# Constant_Current.net
KiCad netlist of a schematic drawn in Altium Designer
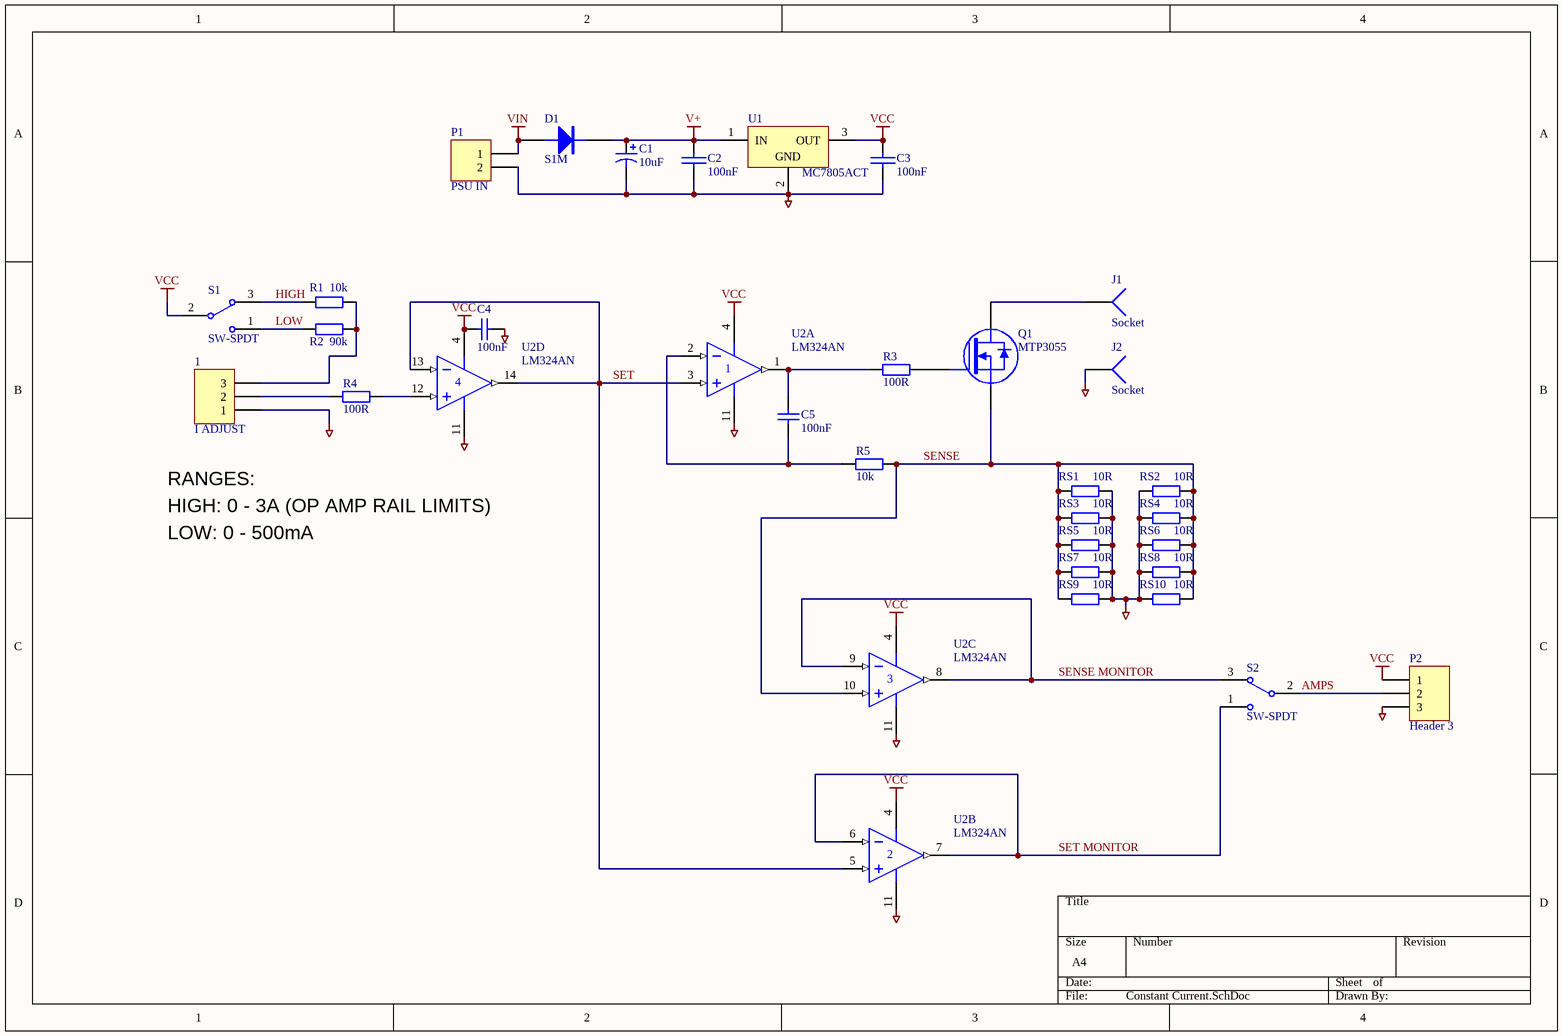
[diagram p0: Constant Current.SchDoc]

(export (version "E")
  (design (tool "Eeschema 10.0.6"))
  (components
    (comp (ref "1")
      (value "I ADJUST")
      (footprint "PCB POT 17MM")
      (description "Header, 3-Pin")
      (fields (field (name "PUBLISHER") "Altium Limited"))
      (libsource (lib "Miscellaneous Connectors") (part "Header 3"))
    )
    (comp (ref "C1")
      (value "10uF")
      (footprint "CAP E CASE")
      (description "Polarized Capacitor (Radial)")
      (libsource (lib "Miscellaneous Devices") (part "Cap Pol1"))
    )
    (comp (ref "C2")
      (value "100nF")
      (footprint "LowCostLabs:CAP 0805")
      (description "CAPACITOR SMD 0603")
      (fields (field (name "MOUSER PART NO.") "81-GCM188R71C104KA7D") (field (name "MANUFACTURER") "Murata"))
      (libsource (lib "Mi-Call Schematic") (part "CAP"))
    )
    (comp (ref "C3")
      (value "100nF")
      (footprint "LowCostLabs:CAP 0805")
      (description "CAPACITOR SMD 0603")
      (fields (field (name "MOUSER PART NO.") "81-GCM188R71C104KA7D") (field (name "MANUFACTURER") "Murata"))
      (libsource (lib "Mi-Call Schematic") (part "CAP"))
    )
    (comp (ref "C4")
      (value "100nF")
      (footprint "LowCostLabs:CAP 0805")
      (description "Capacitor")
      (fields
        (field (name "MANUFACTURER") "YAEGO")
        (field (name "MANUFACTURER PART NO.") "CC0603ZRY5V9BB104")
      )
      (libsource (lib "Miscellaneous Devices") (part "Cap"))
    )
    (comp (ref "C5")
      (value "100nF")
      (footprint "LowCostLabs:CAP 0805")
      (description "Capacitor")
      (fields
        (field (name "MANUFACTURER") "YAEGO")
        (field (name "MANUFACTURER PART NO.") "CC0603ZRY5V9BB104")
      )
      (libsource (lib "Miscellaneous Devices") (part "Cap"))
    )
    (comp (ref "D1")
      (value "S1M")
      (footprint "DO-214AC")
      (description "DIODE, POWER")
      (fields (field (name "MOUSER PART NO.") "821-S1M") (field (name "MANUFACTURER") "Taiwan Semiconductor"))
      (libsource (lib "*") (part "DIODE"))
    )
    (comp (ref "J1")
      (value "Socket")
      (footprint "TP")
      (fields (field (name "PUBLISHER") "Altium Limited"))
      (libsource (lib "Miscellaneous Connectors") (part "Socket"))
    )
    (comp (ref "J2")
      (value "Socket")
      (footprint "TP")
      (fields (field (name "PUBLISHER") "Altium Limited"))
      (libsource (lib "Miscellaneous Connectors") (part "Socket"))
    )
    (comp (ref "P1")
      (value "PSU IN")
      (footprint "5.08mm HEADER 2 Way RA- With Socket")
      (description "Header, 2-Pin")
      (fields (field (name "PUBLISHER") "Altium Limited"))
      (libsource (lib "Miscellaneous Connectors") (part "Header 2"))
    )
    (comp (ref "P2")
      (value "Header 3")
      (footprint "HDR1X3")
      (description "Header, 3-Pin")
      (fields (field (name "PUBLISHER") "Altium Limited"))
      (libsource (lib "") (part "Header 3_1"))
    )
    (comp (ref "Q1")
      (value "MTP3055")
      (footprint "TO-220AB")
      (description "N-Channel MOSFET")
      (libsource (lib "Schlib1") (part "MOSFET-N4"))
    )
    (comp (ref "R1")
      (value "10k")
      (footprint "LowCostLabs:RES 0805")
      (description "Resistor")
      (fields (field (name "Comment") "0805"))
      (libsource (lib "") (part "Res2_1"))
    )
    (comp (ref "R2")
      (value "90k")
      (footprint "LowCostLabs:RES 0805")
      (description "Resistor")
      (fields (field (name "Comment") "0805"))
      (libsource (lib "") (part "Res2_1"))
    )
    (comp (ref "R3")
      (value "100R")
      (footprint "LowCostLabs:RES 0805")
      (description "Resistor")
      (fields (field (name "Comment") "0805"))
      (libsource (lib "") (part "Res2_1"))
    )
    (comp (ref "R4")
      (value "100R")
      (footprint "LowCostLabs:RES 0805")
      (description "Resistor")
      (fields (field (name "Comment") "0805"))
      (libsource (lib "") (part "Res2_1"))
    )
    (comp (ref "R5")
      (value "10k")
      (footprint "LowCostLabs:RES 0805")
      (description "Resistor")
      (fields (field (name "Comment") "0805"))
      (libsource (lib "") (part "Res2_1"))
    )
    (comp (ref "RS1")
      (value "10R")
      (footprint "LowCostLabs:RES 1210")
      (description "Resistor")
      (fields (field (name "Comment") "0805"))
      (libsource (lib "Miscellaneous Devices") (part "Res2"))
    )
    (comp (ref "RS2")
      (value "10R")
      (footprint "LowCostLabs:RES 1210")
      (description "Resistor")
      (fields (field (name "Comment") "0805"))
      (libsource (lib "Miscellaneous Devices") (part "Res2"))
    )
    (comp (ref "RS3")
      (value "10R")
      (footprint "LowCostLabs:RES 1210")
      (description "Resistor")
      (fields (field (name "Comment") "0805"))
      (libsource (lib "Miscellaneous Devices") (part "Res2"))
    )
    (comp (ref "RS4")
      (value "10R")
      (footprint "LowCostLabs:RES 1210")
      (description "Resistor")
      (fields (field (name "Comment") "0805"))
      (libsource (lib "Miscellaneous Devices") (part "Res2"))
    )
    (comp (ref "RS5")
      (value "10R")
      (footprint "LowCostLabs:RES 1210")
      (description "Resistor")
      (fields (field (name "Comment") "0805"))
      (libsource (lib "Miscellaneous Devices") (part "Res2"))
    )
    (comp (ref "RS6")
      (value "10R")
      (footprint "LowCostLabs:RES 1210")
      (description "Resistor")
      (fields (field (name "Comment") "0805"))
      (libsource (lib "Miscellaneous Devices") (part "Res2"))
    )
    (comp (ref "RS7")
      (value "10R")
      (footprint "LowCostLabs:RES 1210")
      (description "Resistor")
      (fields (field (name "Comment") "0805"))
      (libsource (lib "Miscellaneous Devices") (part "Res2"))
    )
    (comp (ref "RS8")
      (value "10R")
      (footprint "LowCostLabs:RES 1210")
      (description "Resistor")
      (fields (field (name "Comment") "0805"))
      (libsource (lib "Miscellaneous Devices") (part "Res2"))
    )
    (comp (ref "RS9")
      (value "10R")
      (footprint "LowCostLabs:RES 1210")
      (description "Resistor")
      (fields (field (name "Comment") "0805"))
      (libsource (lib "Miscellaneous Devices") (part "Res2"))
    )
    (comp (ref "RS10")
      (value "10R")
      (footprint "LowCostLabs:RES 1210")
      (description "Resistor")
      (fields (field (name "Comment") "0805"))
      (libsource (lib "Miscellaneous Devices") (part "Res2"))
    )
    (comp (ref "S1")
      (value "SW-SPDT")
      (footprint "SPDT MINI TOGGLE (BOARD MOUNT)")
      (description "SPDT Subminiature Toggle Switch, Right Angle Mounting, Vertical Actuation")
      (fields (field (name "PUBLISHER") "Altium Limited"))
      (libsource (lib "Miscellaneous Devices") (part "SW-SPDT"))
    )
    (comp (ref "S2")
      (value "SW-SPDT")
      (footprint "SPDT MINI TOGGLE (BOARD MOUNT)")
      (description "SPDT Subminiature Toggle Switch, Right Angle Mounting, Vertical Actuation")
      (fields (field (name "PUBLISHER") "Altium Limited"))
      (libsource (lib "Miscellaneous Devices") (part "SW-SPDT"))
    )
    (comp (ref "U1")
      (value "MC7805ACT")
      (footprint "SOT89")
      (description "3-Terminal Positive Fixed Voltage Regulator")
      (fields
        (field (name "MOUSER PART NO.") "512-LM7805ACT")
        (field (name "MANUFACTURER") "Fairchild Semiconductor")
      )
      (libsource (lib "Motorola Power Mgt Voltage Regulator") (part "MC7805ACT"))
    )
    (comp (ref "U2")
      (value "LM324AN")
      (footprint "LowCostLabs:SOIC-14")
      (description "Quadruple Operational Amplifier")
      (fields (field (name "MANUFACTURER") "ST MICRO") (field (name "MOUSER PART NO.") "511-LM324AN"))
      (libsource (lib "TI Operational Amplifier") (part "LM324AN"))
    )
  )
  (nets
    (net (code "1") (name "/AMPS") (class "Default")
      (node (ref "P2") (pin "2") (pinfunction "2_2") (pintype "passive"))
      (node (ref "S2") (pin "2") (pinfunction "2_2") (pintype "passive"))
    )
    (net (code "2") (name "/HIGH") (class "Default")
      (node (ref "R1") (pin "1") (pinfunction "1_1") (pintype "passive"))
      (node (ref "S1") (pin "3") (pinfunction "3_3") (pintype "passive"))
    )
    (net (code "3") (name "/LOW") (class "Default")
      (node (ref "R2") (pin "1") (pinfunction "1_1") (pintype "passive"))
      (node (ref "S1") (pin "1") (pinfunction "1_1") (pintype "passive"))
    )
    (net (code "4") (name "/SENSE") (class "Default")
      (node (ref "Q1") (pin "3") (pinfunction "S_3") (pintype "passive"))
      (node (ref "R5") (pin "2") (pinfunction "2_2") (pintype "passive"))
      (node (ref "RS1") (pin "2") (pinfunction "2_2") (pintype "passive"))
      (node (ref "RS10") (pin "1") (pinfunction "1_1") (pintype "passive"))
      (node (ref "RS2") (pin "1") (pinfunction "1_1") (pintype "passive"))
      (node (ref "RS3") (pin "2") (pinfunction "2_2") (pintype "passive"))
      (node (ref "RS4") (pin "1") (pinfunction "1_1") (pintype "passive"))
      (node (ref "RS5") (pin "2") (pinfunction "2_2") (pintype "passive"))
      (node (ref "RS6") (pin "1") (pinfunction "1_1") (pintype "passive"))
      (node (ref "RS7") (pin "2") (pinfunction "2_2") (pintype "passive"))
      (node (ref "RS8") (pin "1") (pinfunction "1_1") (pintype "passive"))
      (node (ref "RS9") (pin "2") (pinfunction "2_2") (pintype "passive"))
      (node (ref "U2") (pin "10") (pinfunction "IN+_10") (pintype "input"))
    )
    (net (code "5") (name "/SENSE MONITOR") (class "Default")
      (node (ref "S2") (pin "3") (pinfunction "3_3") (pintype "passive"))
      (node (ref "U2") (pin "8") (pinfunction "OUT_8") (pintype "output"))
      (node (ref "U2") (pin "9") (pinfunction "IN-_9") (pintype "input"))
    )
    (net (code "6") (name "/SET") (class "Default")
      (node (ref "U2") (pin "13") (pinfunction "IN-_13") (pintype "input"))
      (node (ref "U2") (pin "14") (pinfunction "OUT_14") (pintype "output"))
      (node (ref "U2") (pin "3") (pinfunction "IN+_3") (pintype "input"))
      (node (ref "U2") (pin "5") (pinfunction "IN+_5") (pintype "input"))
    )
    (net (code "7") (name "/SET MONITOR") (class "Default")
      (node (ref "S2") (pin "1") (pinfunction "1_1") (pintype "passive"))
      (node (ref "U2") (pin "6") (pinfunction "IN-_6") (pintype "input"))
      (node (ref "U2") (pin "7") (pinfunction "OUT_7") (pintype "output"))
    )
    (net (code "8") (name "GND") (class "Default")
      (node (ref "1") (pin "1") (pinfunction "1_1") (pintype "passive"))
      (node (ref "C1") (pin "2") (pinfunction "2_2") (pintype "passive"))
      (node (ref "C2") (pin "2") (pinfunction "2_2") (pintype "passive"))
      (node (ref "C3") (pin "2") (pinfunction "2_2") (pintype "passive"))
      (node (ref "C4") (pin "1") (pinfunction "1_1") (pintype "passive"))
      (node (ref "J2") (pin "1") (pinfunction "1_1") (pintype "passive"))
      (node (ref "P1") (pin "2") (pinfunction "2_2") (pintype "passive"))
      (node (ref "P2") (pin "3") (pinfunction "3_3") (pintype "passive"))
      (node (ref "RS1") (pin "1") (pinfunction "1_1") (pintype "passive"))
      (node (ref "RS10") (pin "2") (pinfunction "2_2") (pintype "passive"))
      (node (ref "RS2") (pin "2") (pinfunction "2_2") (pintype "passive"))
      (node (ref "RS3") (pin "1") (pinfunction "1_1") (pintype "passive"))
      (node (ref "RS4") (pin "2") (pinfunction "2_2") (pintype "passive"))
      (node (ref "RS5") (pin "1") (pinfunction "1_1") (pintype "passive"))
      (node (ref "RS6") (pin "2") (pinfunction "2_2") (pintype "passive"))
      (node (ref "RS7") (pin "1") (pinfunction "1_1") (pintype "passive"))
      (node (ref "RS8") (pin "2") (pinfunction "2_2") (pintype "passive"))
      (node (ref "RS9") (pin "1") (pinfunction "1_1") (pintype "passive"))
      (node (ref "U1") (pin "2") (pinfunction "GND_2") (pintype "power_in"))
      (node (ref "U2") (pin "11") (pinfunction "V-_11") (pintype "power_in"))
    )
    (net (code "9") (name "Net-(1-Pad2)") (class "Default")
      (node (ref "1") (pin "2") (pinfunction "2_2") (pintype "passive"))
      (node (ref "R4") (pin "1") (pinfunction "1_1") (pintype "passive"))
    )
    (net (code "10") (name "Net-(1-Pad3)") (class "Default")
      (node (ref "1") (pin "3") (pinfunction "3_3") (pintype "passive"))
      (node (ref "R1") (pin "2") (pinfunction "2_2") (pintype "passive"))
      (node (ref "R2") (pin "2") (pinfunction "2_2") (pintype "passive"))
    )
    (net (code "11") (name "Net-(Q1-D)") (class "Default")
      (node (ref "J1") (pin "1") (pinfunction "1_1") (pintype "passive"))
      (node (ref "Q1") (pin "2") (pinfunction "D_2") (pintype "passive"))
    )
    (net (code "12") (name "Net-(Q1-G)") (class "Default")
      (node (ref "Q1") (pin "1") (pinfunction "G_1") (pintype "passive"))
      (node (ref "R3") (pin "2") (pinfunction "2_2") (pintype "passive"))
    )
    (net (code "13") (name "Net-(U2A-IN-)") (class "Default")
      (node (ref "C5") (pin "2") (pinfunction "2_2") (pintype "passive"))
      (node (ref "R5") (pin "1") (pinfunction "1_1") (pintype "passive"))
      (node (ref "U2") (pin "2") (pinfunction "IN-_2") (pintype "input"))
    )
    (net (code "14") (name "Net-(U2A-OUT)") (class "Default")
      (node (ref "C5") (pin "1") (pinfunction "1_1") (pintype "passive"))
      (node (ref "R3") (pin "1") (pinfunction "1_1") (pintype "passive"))
      (node (ref "U2") (pin "1") (pinfunction "OUT_1") (pintype "output"))
    )
    (net (code "15") (name "Net-(U2D-IN+)") (class "Default")
      (node (ref "R4") (pin "2") (pinfunction "2_2") (pintype "passive"))
      (node (ref "U2") (pin "12") (pinfunction "IN+_12") (pintype "input"))
    )
    (net (code "16") (name "V+") (class "Default")
      (node (ref "C1") (pin "1") (pinfunction "1_1") (pintype "passive"))
      (node (ref "C2") (pin "1") (pinfunction "1_1") (pintype "passive"))
      (node (ref "D1") (pin "2") (pinfunction "K_2") (pintype "passive"))
      (node (ref "U1") (pin "1") (pinfunction "IN_1") (pintype "power_in"))
    )
    (net (code "17") (name "VCC") (class "Default")
      (node (ref "C3") (pin "1") (pinfunction "1_1") (pintype "passive"))
      (node (ref "C4") (pin "2") (pinfunction "2_2") (pintype "passive"))
      (node (ref "P2") (pin "1") (pinfunction "1_1") (pintype "passive"))
      (node (ref "S1") (pin "2") (pinfunction "2_2") (pintype "passive"))
      (node (ref "U1") (pin "3") (pinfunction "OUT_3") (pintype "power_in"))
      (node (ref "U2") (pin "4") (pinfunction "V+_4") (pintype "power_in"))
    )
    (net (code "18") (name "VIN") (class "Default")
      (node (ref "D1") (pin "1") (pinfunction "A_1") (pintype "passive"))
      (node (ref "P1") (pin "1") (pinfunction "1_1") (pintype "passive"))
    )
  )
)
